# Cpcis_connectors_P1_P6.net
KiCad netlist of a schematic drawn in Altium Designer
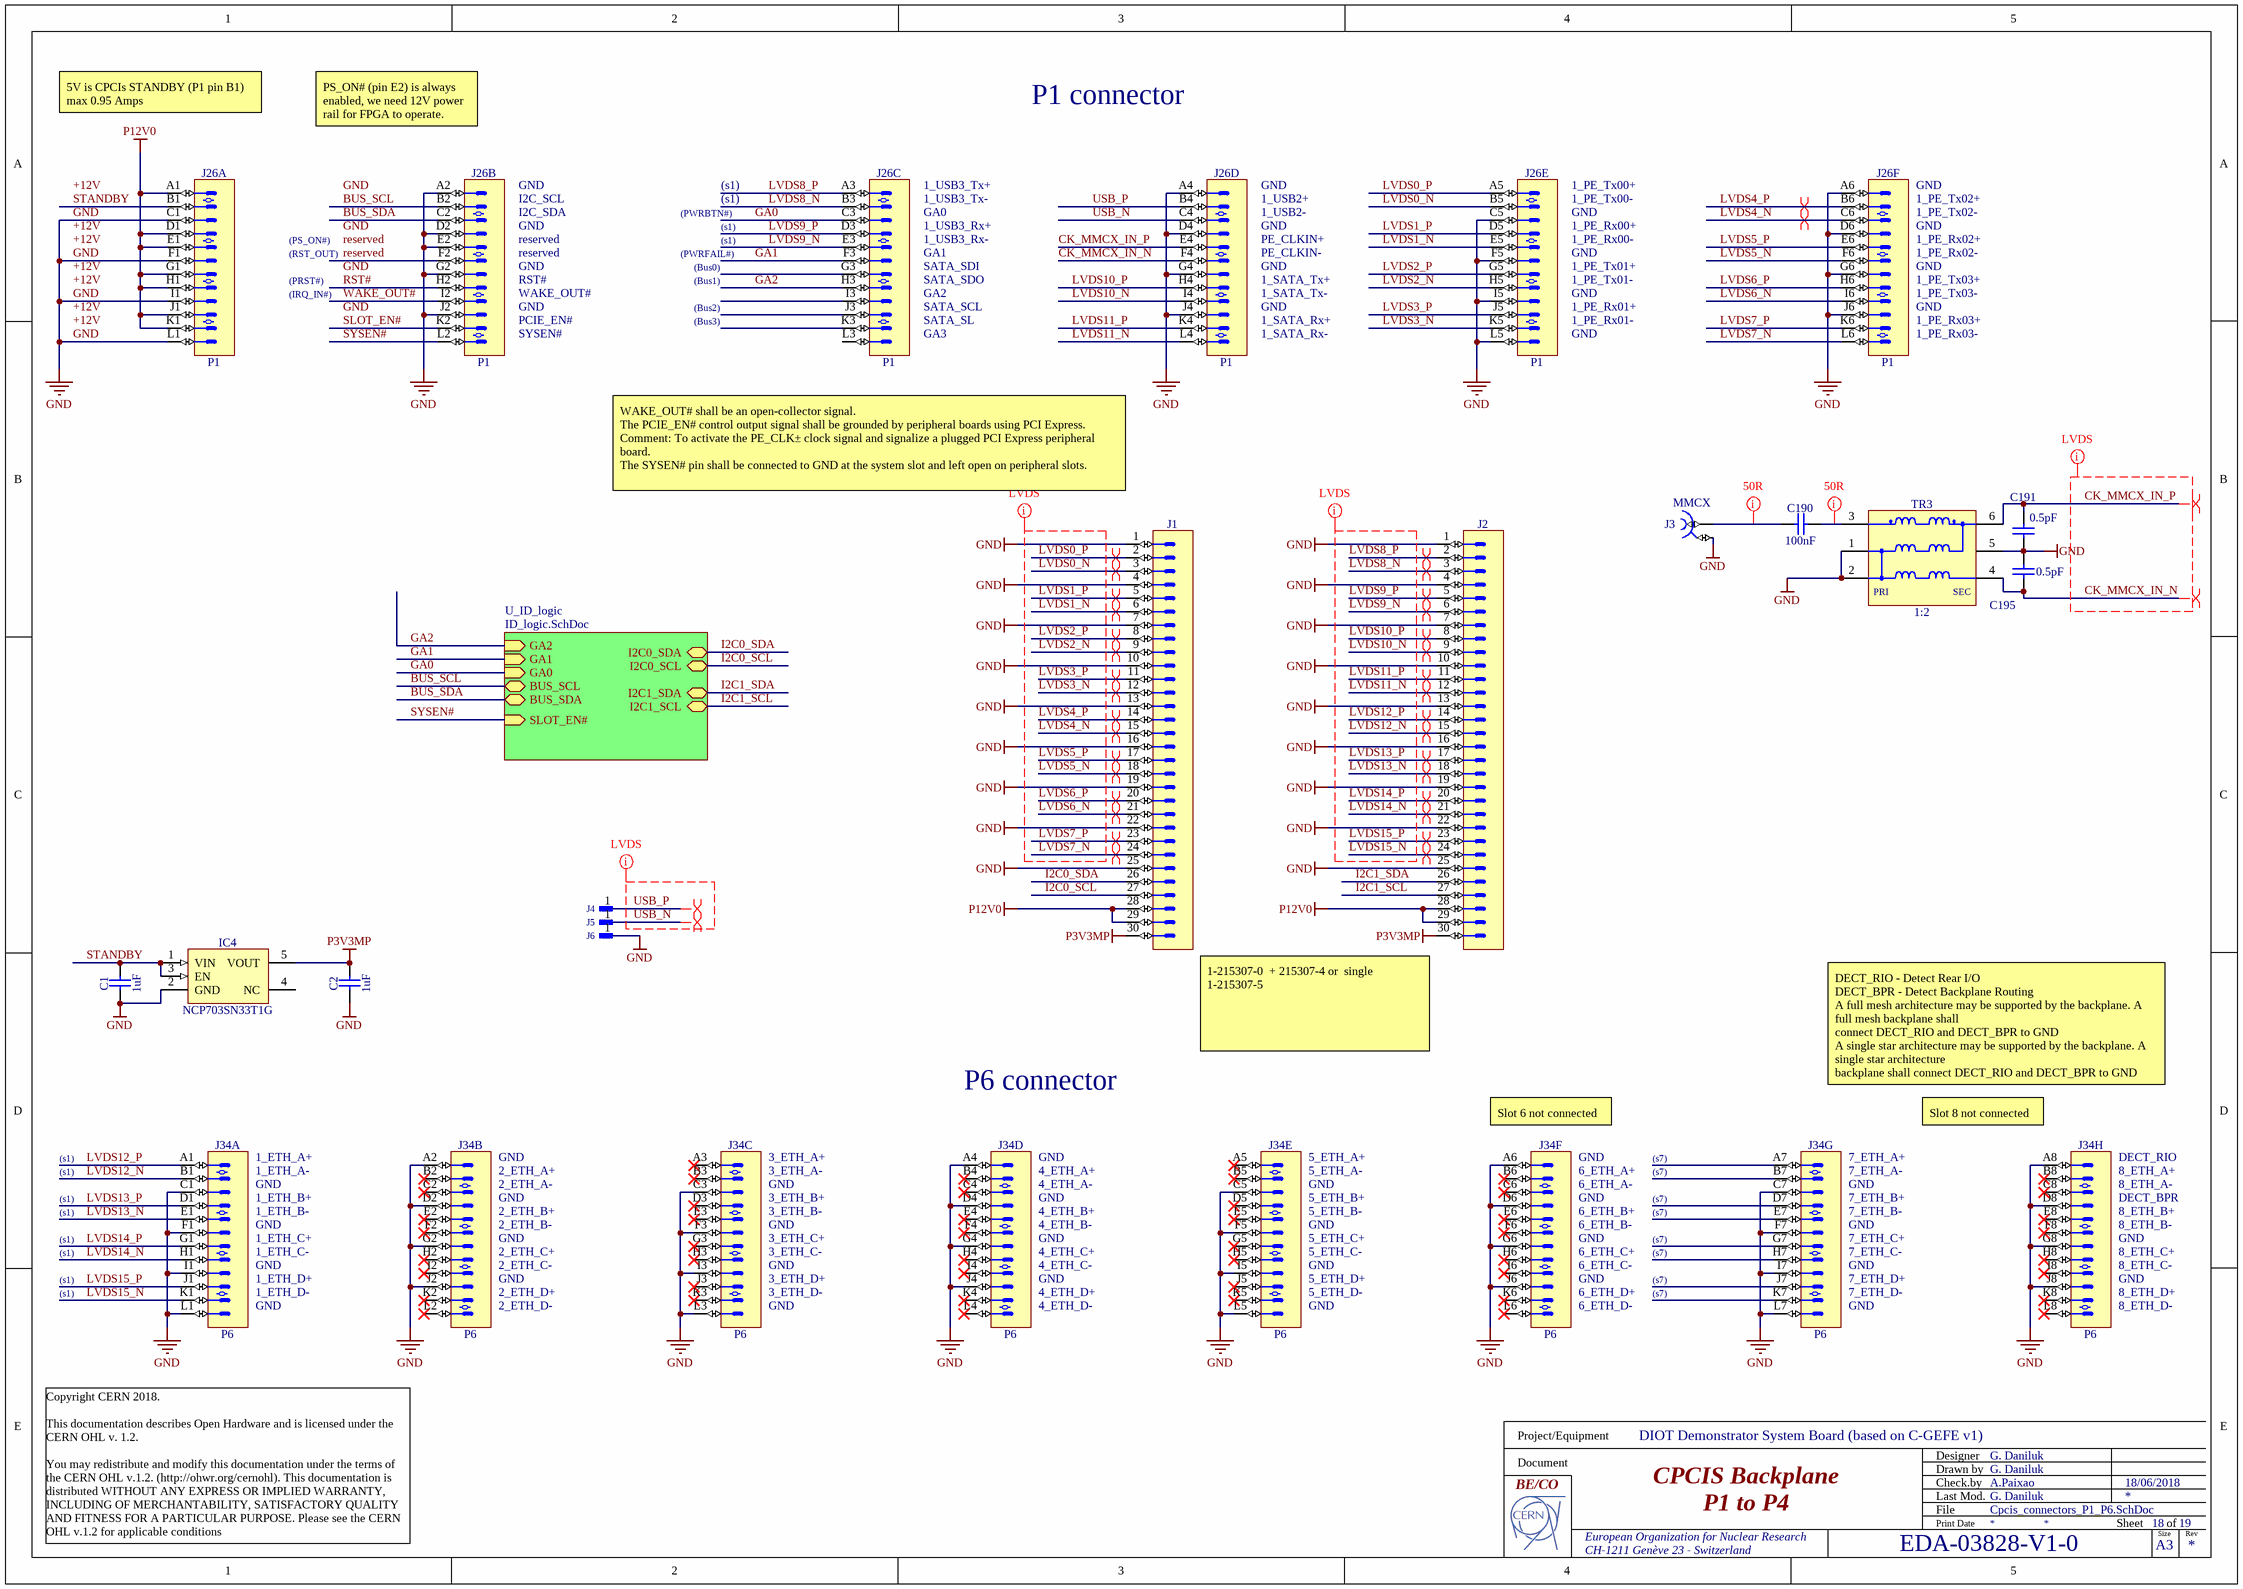
[diagram p0: Cpcis_connectors_P1_P6.SchDoc]

(export (version "E")
  (design (tool "Eeschema 10.0.6"))
  (components
    (comp (ref "C1")
      (value "1uF")
      (footprint "CAPC2012X140N")
      (description "Non-polarised capacitor")
      (fields
        (field (name "PART NUMBER") "CC0805_1UF_35V_20%_X7R")
        (field (name "VOLTAGE") "35V")
        (field (name "AUTHOR") "CERN DEM JLC")
      )
      (libsource (lib "Capacitors") (part "Capacitor - non polarized"))
    )
    (comp (ref "C2")
      (value "1uF")
      (footprint "CAPC2012X140N")
      (description "Non-polarised capacitor")
      (fields
        (field (name "PART NUMBER") "CC0805_1UF_35V_20%_X7R")
        (field (name "VOLTAGE") "35V")
        (field (name "AUTHOR") "CERN DEM JLC")
      )
      (libsource (lib "Capacitors") (part "Capacitor - non polarized"))
    )
    (comp (ref "C190")
      (value "100nF")
      (footprint "CAPC1005X55N")
      (description "Non-polarised capacitor")
      (fields
        (field (name "PART NUMBER") "CC0402_100NF_16V_10%_X5R")
        (field (name "VOLTAGE") "16V")
        (field (name "AUTHOR") "CERN DEM JLC")
      )
      (libsource (lib "Capacitors") (part "Capacitor - non polarized"))
    )
    (comp (ref "C191")
      (value "0.5pF")
      (footprint "CAPC1005X50N")
      (description "Non-polarised capacitor")
      (fields
        (field (name "PART NUMBER") "CC0402_0.5PF_25V_0.05PF_AVX_04023J0R5ABSTR")
        (field (name "VOLTAGE") "25V")
        (field (name "AUTHOR") "CERN DEM JLC")
      )
      (libsource (lib "Capacitors") (part "Capacitor - non polarized"))
    )
    (comp (ref "C195")
      (value "0.5pF")
      (footprint "CAPC1005X50N")
      (description "Non-polarised capacitor")
      (fields
        (field (name "PART NUMBER") "CC0402_0.5PF_25V_0.05PF_AVX_04023J0R5ABSTR")
        (field (name "VOLTAGE") "25V")
        (field (name "AUTHOR") "CERN DEM JLC")
      )
      (libsource (lib "Capacitors") (part "Capacitor - non polarized"))
    )
    (comp (ref "IC4")
      (value "NCP703SN33T1G")
      (footprint "SOT95P275X110-5N")
      (description "3.3V 300mA, Ultra-Low Quiescent Current, IQ 12uA, Ultra-Low Noise, LDO Voltage Regulator")
      (fields (field (name "MANUFACTURER") "ON SEMICONDUCTOR") (field (name "AUTHOR") "CERN DEM JLC"))
      (libsource (lib "ICs And Semiconductors") (part "NCP703SN"))
    )
    (comp (ref "J1")
      (value "AMPMODU")
      (footprint "TYCO_1-215307-5")
      (description "Connector 2.54mm, 30 pin female, vertical, 7mm, AMPMODU HV-100/HV-190")
      (fields
        (field (name "PART NUMBER") "TYCO_1-215307-5")
        (field (name "MANUFACTURER") "TYCO ELECTRONICS")
        (field (name "AUTHOR") "GK")
      )
      (libsource (lib "LIBRARY_SCH") (part "CON_2x15_2.54_female_V_mirror"))
    )
    (comp (ref "J2")
      (value "AMPMODU")
      (footprint "TYCO_1-215307-5")
      (description "Connector 2.54mm, 30 pin female, vertical, 7mm, AMPMODU HV-100/HV-190")
      (fields
        (field (name "PART NUMBER") "TYCO_1-215307-5")
        (field (name "MANUFACTURER") "TYCO ELECTRONICS")
        (field (name "AUTHOR") "GK")
      )
      (libsource (lib "LIBRARY_SCH") (part "CON_2x15_2.54_female_V_mirror"))
    )
    (comp (ref "J3")
      (value "Coax_1Female_1Shield")
      (footprint "HUBER-SUHNER_85_MMCX-50-0-1/111_OE")
      (fields
        (field (name "PART NUMBER") "HUBER-SUHNER_85_MMCX-50-0-1/111_OE")
        (field (name "FAMILY") "MMCX")
        (field (name "MANUFACTURER") "HUBER+SUHNER")
        (field (name "MANUFACTURER PART NUMBER") "85_MMCX-50-0-1/111_OE")
        (field (name "AUTHOR") "CERN DEM JLC")
      )
      (libsource (lib "Connectors") (part "Coax_1Female_1Shield"))
    )
    (comp (ref "J4")
      (value "SMD Pad")
      (footprint "R700X200")
      (description "Single SMD Pad Standard")
      (fields (field (name "PART NUMBER") "TEST1_CompoKind") (field (name "AUTHOR") "CERN DEM MR"))
      (libsource (lib "Eletro-mechanical") (part "Single SMD Pad Standard"))
    )
    (comp (ref "J5")
      (value "SMD Pad")
      (footprint "R700X200")
      (description "Single SMD Pad Standard")
      (fields (field (name "PART NUMBER") "TEST1_CompoKind") (field (name "AUTHOR") "CERN DEM MR"))
      (libsource (lib "Eletro-mechanical") (part "Single SMD Pad Standard"))
    )
    (comp (ref "J6")
      (value "SMD Pad")
      (footprint "R700X200")
      (description "Single SMD Pad Standard")
      (fields (field (name "PART NUMBER") "TEST1_CompoKind") (field (name "AUTHOR") "CERN DEM MR"))
      (libsource (lib "Eletro-mechanical") (part "Single SMD Pad Standard"))
    )
    (comp (ref "J26")
      (value "P1")
      (footprint "AMPHENOL_10052825-101LF")
      (description "72 Contacts Header, 6 Columns, 4 Pairs per Column")
      (fields
        (field (name "PART NUMBER") "AMPHENOL_10052825-101LF")
        (field (name "MANUFACTURER") "AMPHENOL")
        (field (name "AUTHOR") "CERN DEM MR")
      )
      (libsource (lib "Connectors") (part "AMPHENOL_10052825-101LF"))
    )
    (comp (ref "J34")
      (value "P6")
      (footprint "AMPHENOL_10052838-101LF")
      (description "96 Contacts Header, 8 Columns, 4 Pairs per Column")
      (fields
        (field (name "PART NUMBER") "AMPHENOL_10052838-101LF")
        (field (name "MANUFACTURER") "AMPHENOL")
        (field (name "AUTHOR") "CERN DEM MR")
      )
      (libsource (lib "Connectors") (part "AMPHENOL_10052838-101LF"))
    )
    (comp (ref "TR3")
      (value "1:2")
      (footprint "XFMR_MINI-CIRCUITS_DB1627")
      (description "50 OHMS 10 to 4000 MHz RF Transformer")
      (fields
        (field (name "PART NUMBER") "XFMR_MINI-CIRCUITS_TCM2-43X+")
        (field (name "POWER") "0.4W")
        (field (name "AUTHOR") "CERN DEM BC")
      )
      (libsource (lib "Inductors & Transformers") (part "XFMR_MINI-CIRCUITS_TCM2-43X"))
    )
  )
  (nets
    (net (code "2") (name "/BUS_SCL") (class "Default")
      (node (ref "J26") (pin "B2") (pinfunction "B2_B2") (pintype "bidirectional"))
    )
    (net (code "3") (name "/BUS_SDA") (class "Default")
      (node (ref "J26") (pin "C2") (pinfunction "C2_C2") (pintype "bidirectional"))
    )
    (net (code "4") (name "/CK_MMCX_IN_N") (class "Default")
      (node (ref "C195") (pin "1") (pinfunction "1_1") (pintype "passive"))
      (node (ref "J26") (pin "F4") (pinfunction "F4_F4") (pintype "bidirectional"))
      (node (ref "TR3") (pin "4") (pinfunction "S1_4") (pintype "passive"))
    )
    (net (code "5") (name "/CK_MMCX_IN_P") (class "Default")
      (node (ref "C191") (pin "2") (pinfunction "2_2") (pintype "passive"))
      (node (ref "J26") (pin "E4") (pinfunction "E4_E4") (pintype "bidirectional"))
      (node (ref "TR3") (pin "6") (pinfunction "S1_6") (pintype "passive"))
    )
    (net (code "6") (name "/GA0") (class "Default")
      (node (ref "J26") (pin "C3") (pinfunction "C3_C3") (pintype "bidirectional"))
    )
    (net (code "7") (name "/GA1") (class "Default")
      (node (ref "J26") (pin "F3") (pinfunction "F3_F3") (pintype "bidirectional"))
    )
    (net (code "8") (name "/GA2") (class "Default")
      (node (ref "J26") (pin "H3") (pinfunction "H3_H3") (pintype "bidirectional"))
    )
    (net (code "9") (name "/I2C0_SCL") (class "Default")
      (node (ref "J1") (pin "27") (pinfunction "27_27") (pintype "bidirectional"))
    )
    (net (code "10") (name "/I2C0_SDA") (class "Default")
      (node (ref "J1") (pin "26") (pinfunction "26_26") (pintype "bidirectional"))
    )
    (net (code "11") (name "/I2C1_SCL") (class "Default")
      (node (ref "J2") (pin "27") (pinfunction "27_27") (pintype "bidirectional"))
    )
    (net (code "12") (name "/I2C1_SDA") (class "Default")
      (node (ref "J2") (pin "26") (pinfunction "26_26") (pintype "bidirectional"))
    )
    (net (code "13") (name "/LVDS0_N") (class "Default")
      (node (ref "J1") (pin "3") (pinfunction "3_3") (pintype "bidirectional"))
      (node (ref "J26") (pin "B5") (pinfunction "B5_B5") (pintype "bidirectional"))
    )
    (net (code "14") (name "/LVDS0_P") (class "Default")
      (node (ref "J1") (pin "2") (pinfunction "2_2") (pintype "bidirectional"))
      (node (ref "J26") (pin "A5") (pinfunction "A5_A5") (pintype "bidirectional"))
    )
    (net (code "15") (name "/LVDS1_N") (class "Default")
      (node (ref "J1") (pin "6") (pinfunction "6_6") (pintype "bidirectional"))
      (node (ref "J26") (pin "E5") (pinfunction "E5_E5") (pintype "bidirectional"))
    )
    (net (code "16") (name "/LVDS1_P") (class "Default")
      (node (ref "J1") (pin "5") (pinfunction "5_5") (pintype "bidirectional"))
      (node (ref "J26") (pin "D5") (pinfunction "D5_D5") (pintype "bidirectional"))
    )
    (net (code "17") (name "/LVDS2_N") (class "Default")
      (node (ref "J1") (pin "9") (pinfunction "9_9") (pintype "bidirectional"))
      (node (ref "J26") (pin "H5") (pinfunction "H5_H5") (pintype "bidirectional"))
    )
    (net (code "18") (name "/LVDS2_P") (class "Default")
      (node (ref "J1") (pin "8") (pinfunction "8_8") (pintype "bidirectional"))
      (node (ref "J26") (pin "G5") (pinfunction "G5_G5") (pintype "bidirectional"))
    )
    (net (code "19") (name "/LVDS3_N") (class "Default")
      (node (ref "J1") (pin "12") (pinfunction "12_12") (pintype "bidirectional"))
      (node (ref "J26") (pin "K5") (pinfunction "K5_K5") (pintype "bidirectional"))
    )
    (net (code "20") (name "/LVDS3_P") (class "Default")
      (node (ref "J1") (pin "11") (pinfunction "11_11") (pintype "bidirectional"))
      (node (ref "J26") (pin "J5") (pinfunction "J5_J5") (pintype "bidirectional"))
    )
    (net (code "21") (name "/LVDS4_N") (class "Default")
      (node (ref "J1") (pin "15") (pinfunction "15_15") (pintype "bidirectional"))
      (node (ref "J26") (pin "C6") (pinfunction "C6_C6") (pintype "bidirectional"))
    )
    (net (code "22") (name "/LVDS4_P") (class "Default")
      (node (ref "J1") (pin "14") (pinfunction "14_14") (pintype "bidirectional"))
      (node (ref "J26") (pin "B6") (pinfunction "B6_B6") (pintype "bidirectional"))
    )
    (net (code "23") (name "/LVDS5_N") (class "Default")
      (node (ref "J1") (pin "18") (pinfunction "18_18") (pintype "bidirectional"))
      (node (ref "J26") (pin "F6") (pinfunction "F6_F6") (pintype "bidirectional"))
    )
    (net (code "24") (name "/LVDS5_P") (class "Default")
      (node (ref "J1") (pin "17") (pinfunction "17_17") (pintype "bidirectional"))
      (node (ref "J26") (pin "E6") (pinfunction "E6_E6") (pintype "bidirectional"))
    )
    (net (code "25") (name "/LVDS6_N") (class "Default")
      (node (ref "J1") (pin "21") (pinfunction "21_21") (pintype "bidirectional"))
      (node (ref "J26") (pin "I6") (pinfunction "I6_I6") (pintype "bidirectional"))
    )
    (net (code "26") (name "/LVDS6_P") (class "Default")
      (node (ref "J1") (pin "20") (pinfunction "20_20") (pintype "bidirectional"))
      (node (ref "J26") (pin "H6") (pinfunction "H6_H6") (pintype "bidirectional"))
    )
    (net (code "27") (name "/LVDS7_N") (class "Default")
      (node (ref "J1") (pin "24") (pinfunction "24_24") (pintype "bidirectional"))
      (node (ref "J26") (pin "L6") (pinfunction "L6_L6") (pintype "bidirectional"))
    )
    (net (code "28") (name "/LVDS7_P") (class "Default")
      (node (ref "J1") (pin "23") (pinfunction "23_23") (pintype "bidirectional"))
      (node (ref "J26") (pin "K6") (pinfunction "K6_K6") (pintype "bidirectional"))
    )
    (net (code "29") (name "/LVDS8_N") (class "Default")
      (node (ref "J2") (pin "3") (pinfunction "3_3") (pintype "bidirectional"))
      (node (ref "J26") (pin "B3") (pinfunction "B3_B3") (pintype "bidirectional"))
    )
    (net (code "30") (name "/LVDS8_P") (class "Default")
      (node (ref "J2") (pin "2") (pinfunction "2_2") (pintype "bidirectional"))
      (node (ref "J26") (pin "A3") (pinfunction "A3_A3") (pintype "bidirectional"))
    )
    (net (code "31") (name "/LVDS9_N") (class "Default")
      (node (ref "J2") (pin "6") (pinfunction "6_6") (pintype "bidirectional"))
      (node (ref "J26") (pin "E3") (pinfunction "E3_E3") (pintype "bidirectional"))
    )
    (net (code "32") (name "/LVDS9_P") (class "Default")
      (node (ref "J2") (pin "5") (pinfunction "5_5") (pintype "bidirectional"))
      (node (ref "J26") (pin "D3") (pinfunction "D3_D3") (pintype "bidirectional"))
    )
    (net (code "33") (name "/LVDS10_N") (class "Default")
      (node (ref "J2") (pin "9") (pinfunction "9_9") (pintype "bidirectional"))
      (node (ref "J26") (pin "I4") (pinfunction "I4_I4") (pintype "bidirectional"))
    )
    (net (code "34") (name "/LVDS10_P") (class "Default")
      (node (ref "J2") (pin "8") (pinfunction "8_8") (pintype "bidirectional"))
      (node (ref "J26") (pin "H4") (pinfunction "H4_H4") (pintype "bidirectional"))
    )
    (net (code "35") (name "/LVDS11_N") (class "Default")
      (node (ref "J2") (pin "12") (pinfunction "12_12") (pintype "bidirectional"))
      (node (ref "J26") (pin "L4") (pinfunction "L4_L4") (pintype "bidirectional"))
    )
    (net (code "36") (name "/LVDS11_P") (class "Default")
      (node (ref "J2") (pin "11") (pinfunction "11_11") (pintype "bidirectional"))
      (node (ref "J26") (pin "K4") (pinfunction "K4_K4") (pintype "bidirectional"))
    )
    (net (code "37") (name "/LVDS12_N") (class "Default")
      (node (ref "J2") (pin "15") (pinfunction "15_15") (pintype "bidirectional"))
      (node (ref "J34") (pin "B1") (pinfunction "B1_B1") (pintype "bidirectional"))
    )
    (net (code "38") (name "/LVDS12_P") (class "Default")
      (node (ref "J2") (pin "14") (pinfunction "14_14") (pintype "bidirectional"))
      (node (ref "J34") (pin "A1") (pinfunction "A1_A1") (pintype "bidirectional"))
    )
    (net (code "39") (name "/LVDS13_N") (class "Default")
      (node (ref "J2") (pin "18") (pinfunction "18_18") (pintype "bidirectional"))
      (node (ref "J34") (pin "E1") (pinfunction "E1_E1") (pintype "bidirectional"))
    )
    (net (code "40") (name "/LVDS13_P") (class "Default")
      (node (ref "J2") (pin "17") (pinfunction "17_17") (pintype "bidirectional"))
      (node (ref "J34") (pin "D1") (pinfunction "D1_D1") (pintype "bidirectional"))
    )
    (net (code "41") (name "/LVDS14_N") (class "Default")
      (node (ref "J2") (pin "21") (pinfunction "21_21") (pintype "bidirectional"))
      (node (ref "J34") (pin "H1") (pinfunction "H1_H1") (pintype "bidirectional"))
    )
    (net (code "42") (name "/LVDS14_P") (class "Default")
      (node (ref "J2") (pin "20") (pinfunction "20_20") (pintype "bidirectional"))
      (node (ref "J34") (pin "G1") (pinfunction "G1_G1") (pintype "bidirectional"))
    )
    (net (code "43") (name "/LVDS15_N") (class "Default")
      (node (ref "J2") (pin "24") (pinfunction "24_24") (pintype "bidirectional"))
      (node (ref "J34") (pin "K1") (pinfunction "K1_K1") (pintype "bidirectional"))
    )
    (net (code "44") (name "/LVDS15_P") (class "Default")
      (node (ref "J2") (pin "23") (pinfunction "23_23") (pintype "bidirectional"))
      (node (ref "J34") (pin "J1") (pinfunction "J1_J1") (pintype "bidirectional"))
    )
    (net (code "45") (name "/RST#") (class "Default")
      (node (ref "J26") (pin "H2") (pinfunction "H2_H2") (pintype "bidirectional"))
    )
    (net (code "46") (name "/SLOT_EN#") (class "Default")
      (node (ref "J26") (pin "K2") (pinfunction "K2_K2") (pintype "bidirectional"))
    )
    (net (code "47") (name "/STANDBY") (class "Default")
      (node (ref "C1") (pin "2") (pinfunction "2_2") (pintype "passive"))
      (node (ref "IC4") (pin "1") (pinfunction "VIN_1") (pintype "input"))
      (node (ref "IC4") (pin "3") (pinfunction "EN_3") (pintype "input"))
      (node (ref "J26") (pin "B1") (pinfunction "B1_B1") (pintype "bidirectional"))
    )
    (net (code "48") (name "/SYSEN#") (class "Default")
      (node (ref "J26") (pin "L2") (pinfunction "L2_L2") (pintype "bidirectional"))
    )
    (net (code "49") (name "/USB_N") (class "Default")
      (node (ref "J26") (pin "C4") (pinfunction "C4_C4") (pintype "bidirectional"))
      (node (ref "J5") (pin "1") (pinfunction "1_1") (pintype "bidirectional"))
    )
    (net (code "50") (name "/USB_P") (class "Default")
      (node (ref "J26") (pin "B4") (pinfunction "B4_B4") (pintype "bidirectional"))
      (node (ref "J4") (pin "1") (pinfunction "1_1") (pintype "bidirectional"))
    )
    (net (code "51") (name "/WAKE_OUT#") (class "Default")
      (node (ref "J26") (pin "I2") (pinfunction "I2_I2") (pintype "bidirectional"))
    )
    (net (code "52") (name "/reserved") (class "Default")
      (node (ref "J26") (pin "F2") (pinfunction "F2_F2") (pintype "bidirectional"))
    )
    (net (code "53") (name "GND") (class "Default")
      (node (ref "C1") (pin "1") (pinfunction "1_1") (pintype "passive"))
      (node (ref "C191") (pin "1") (pinfunction "1_1") (pintype "passive"))
      (node (ref "C195") (pin "2") (pinfunction "2_2") (pintype "passive"))
      (node (ref "C2") (pin "1") (pinfunction "1_1") (pintype "passive"))
      (node (ref "IC4") (pin "2") (pinfunction "GND_2") (pintype "power_in"))
      (node (ref "J1") (pin "1") (pinfunction "1_1") (pintype "bidirectional"))
      (node (ref "J1") (pin "10") (pinfunction "10_10") (pintype "bidirectional"))
      (node (ref "J1") (pin "13") (pinfunction "13_13") (pintype "bidirectional"))
      (node (ref "J1") (pin "16") (pinfunction "16_16") (pintype "bidirectional"))
      (node (ref "J1") (pin "19") (pinfunction "19_19") (pintype "bidirectional"))
      (node (ref "J1") (pin "22") (pinfunction "22_22") (pintype "bidirectional"))
      (node (ref "J1") (pin "25") (pinfunction "25_25") (pintype "bidirectional"))
      (node (ref "J1") (pin "4") (pinfunction "4_4") (pintype "bidirectional"))
      (node (ref "J1") (pin "7") (pinfunction "7_7") (pintype "bidirectional"))
      (node (ref "J2") (pin "1") (pinfunction "1_1") (pintype "bidirectional"))
      (node (ref "J2") (pin "10") (pinfunction "10_10") (pintype "bidirectional"))
      (node (ref "J2") (pin "13") (pinfunction "13_13") (pintype "bidirectional"))
      (node (ref "J2") (pin "16") (pinfunction "16_16") (pintype "bidirectional"))
      (node (ref "J2") (pin "19") (pinfunction "19_19") (pintype "bidirectional"))
      (node (ref "J2") (pin "22") (pinfunction "22_22") (pintype "bidirectional"))
      (node (ref "J2") (pin "25") (pinfunction "25_25") (pintype "bidirectional"))
      (node (ref "J2") (pin "4") (pinfunction "4_4") (pintype "bidirectional"))
      (node (ref "J2") (pin "7") (pinfunction "7_7") (pintype "bidirectional"))
      (node (ref "J26") (pin "A2") (pinfunction "A2_A2") (pintype "bidirectional"))
      (node (ref "J26") (pin "A4") (pinfunction "A4_A4") (pintype "bidirectional"))
      (node (ref "J26") (pin "A6") (pinfunction "A6_A6") (pintype "bidirectional"))
      (node (ref "J26") (pin "C1") (pinfunction "C1_C1") (pintype "bidirectional"))
      (node (ref "J26") (pin "C5") (pinfunction "C5_C5") (pintype "bidirectional"))
      (node (ref "J26") (pin "D2") (pinfunction "D2_D2") (pintype "bidirectional"))
      (node (ref "J26") (pin "D4") (pinfunction "D4_D4") (pintype "bidirectional"))
      (node (ref "J26") (pin "D6") (pinfunction "D6_D6") (pintype "bidirectional"))
      (node (ref "J26") (pin "E2") (pinfunction "E2_E2") (pintype "bidirectional"))
      (node (ref "J26") (pin "F1") (pinfunction "F1_F1") (pintype "bidirectional"))
      (node (ref "J26") (pin "F5") (pinfunction "F5_F5") (pintype "bidirectional"))
      (node (ref "J26") (pin "G2") (pinfunction "G2_G2") (pintype "bidirectional"))
      (node (ref "J26") (pin "G4") (pinfunction "G4_G4") (pintype "bidirectional"))
      (node (ref "J26") (pin "G6") (pinfunction "G6_G6") (pintype "bidirectional"))
      (node (ref "J26") (pin "I1") (pinfunction "I1_I1") (pintype "bidirectional"))
      (node (ref "J26") (pin "I5") (pinfunction "I5_I5") (pintype "bidirectional"))
      (node (ref "J26") (pin "J2") (pinfunction "J2_J2") (pintype "bidirectional"))
      (node (ref "J26") (pin "J4") (pinfunction "J4_J4") (pintype "bidirectional"))
      (node (ref "J26") (pin "J6") (pinfunction "J6_J6") (pintype "bidirectional"))
      (node (ref "J26") (pin "L1") (pinfunction "L1_L1") (pintype "bidirectional"))
      (node (ref "J26") (pin "L5") (pinfunction "L5_L5") (pintype "bidirectional"))
      (node (ref "J3") (pin "2") (pinfunction "2_2") (pintype "bidirectional"))
      (node (ref "J34") (pin "A2") (pinfunction "A2_A2") (pintype "bidirectional"))
      (node (ref "J34") (pin "A4") (pinfunction "A4_A4") (pintype "bidirectional"))
      (node (ref "J34") (pin "A6") (pinfunction "A6_A6") (pintype "bidirectional"))
      (node (ref "J34") (pin "A8") (pinfunction "A8_A8") (pintype "bidirectional"))
      (node (ref "J34") (pin "C1") (pinfunction "C1_C1") (pintype "bidirectional"))
      (node (ref "J34") (pin "C3") (pinfunction "C3_C3") (pintype "bidirectional"))
      (node (ref "J34") (pin "C5") (pinfunction "C5_C5") (pintype "bidirectional"))
      (node (ref "J34") (pin "C7") (pinfunction "C7_C7") (pintype "bidirectional"))
      (node (ref "J34") (pin "D2") (pinfunction "D2_D2") (pintype "bidirectional"))
      (node (ref "J34") (pin "D4") (pinfunction "D4_D4") (pintype "bidirectional"))
      (node (ref "J34") (pin "D6") (pinfunction "D6_D6") (pintype "bidirectional"))
      (node (ref "J34") (pin "D8") (pinfunction "D8_D8") (pintype "bidirectional"))
      (node (ref "J34") (pin "F1") (pinfunction "F1_F1") (pintype "bidirectional"))
      (node (ref "J34") (pin "F3") (pinfunction "F3_F3") (pintype "bidirectional"))
      (node (ref "J34") (pin "F5") (pinfunction "F5_F5") (pintype "bidirectional"))
      (node (ref "J34") (pin "F7") (pinfunction "F7_F7") (pintype "bidirectional"))
      (node (ref "J34") (pin "G2") (pinfunction "G2_G2") (pintype "bidirectional"))
      (node (ref "J34") (pin "G4") (pinfunction "G4_G4") (pintype "bidirectional"))
      (node (ref "J34") (pin "G6") (pinfunction "G6_G6") (pintype "bidirectional"))
      (node (ref "J34") (pin "G8") (pinfunction "G8_G8") (pintype "bidirectional"))
      (node (ref "J34") (pin "I1") (pinfunction "I1_I1") (pintype "bidirectional"))
      (node (ref "J34") (pin "I3") (pinfunction "I3_I3") (pintype "bidirectional"))
      (node (ref "J34") (pin "I5") (pinfunction "I5_I5") (pintype "bidirectional"))
      (node (ref "J34") (pin "I7") (pinfunction "I7_I7") (pintype "bidirectional"))
      (node (ref "J34") (pin "J2") (pinfunction "J2_J2") (pintype "bidirectional"))
      (node (ref "J34") (pin "J4") (pinfunction "J4_J4") (pintype "bidirectional"))
      (node (ref "J34") (pin "J6") (pinfunction "J6_J6") (pintype "bidirectional"))
      (node (ref "J34") (pin "J8") (pinfunction "J8_J8") (pintype "bidirectional"))
      (node (ref "J34") (pin "L1") (pinfunction "L1_L1") (pintype "bidirectional"))
      (node (ref "J34") (pin "L3") (pinfunction "L3_L3") (pintype "bidirectional"))
      (node (ref "J34") (pin "L5") (pinfunction "L5_L5") (pintype "bidirectional"))
      (node (ref "J34") (pin "L7") (pinfunction "L7_L7") (pintype "bidirectional"))
      (node (ref "J6") (pin "1") (pinfunction "1_1") (pintype "bidirectional"))
      (node (ref "TR3") (pin "1") (pinfunction "P1_1") (pintype "passive"))
      (node (ref "TR3") (pin "2") (pinfunction "P1_2") (pintype "passive"))
      (node (ref "TR3") (pin "5") (pinfunction "NC_5") (pintype "passive"))
    )
    (net (code "54") (name "Net-(C190-Pad1)") (class "Default")
      (node (ref "C190") (pin "1") (pinfunction "1_1") (pintype "passive"))
      (node (ref "J3") (pin "1") (pinfunction "1_1") (pintype "bidirectional"))
    )
    (net (code "55") (name "Net-(C190-Pad2)") (class "Default")
      (node (ref "C190") (pin "2") (pinfunction "2_2") (pintype "passive"))
      (node (ref "TR3") (pin "3") (pinfunction "P1_3") (pintype "passive"))
    )
    (net (code "56") (name "P3V3MP") (class "Default")
      (node (ref "C2") (pin "2") (pinfunction "2_2") (pintype "passive"))
      (node (ref "IC4") (pin "5") (pinfunction "VOUT_5") (pintype "power_in"))
      (node (ref "J1") (pin "30") (pinfunction "30_30") (pintype "bidirectional"))
      (node (ref "J2") (pin "30") (pinfunction "30_30") (pintype "bidirectional"))
    )
    (net (code "57") (name "P12V0") (class "Default")
      (node (ref "J1") (pin "28") (pinfunction "28_28") (pintype "bidirectional"))
      (node (ref "J1") (pin "29") (pinfunction "29_29") (pintype "bidirectional"))
      (node (ref "J2") (pin "28") (pinfunction "28_28") (pintype "bidirectional"))
      (node (ref "J2") (pin "29") (pinfunction "29_29") (pintype "bidirectional"))
      (node (ref "J26") (pin "A1") (pinfunction "A1_A1") (pintype "bidirectional"))
      (node (ref "J26") (pin "D1") (pinfunction "D1_D1") (pintype "bidirectional"))
      (node (ref "J26") (pin "E1") (pinfunction "E1_E1") (pintype "bidirectional"))
      (node (ref "J26") (pin "G1") (pinfunction "G1_G1") (pintype "bidirectional"))
      (node (ref "J26") (pin "H1") (pinfunction "H1_H1") (pintype "bidirectional"))
      (node (ref "J26") (pin "J1") (pinfunction "J1_J1") (pintype "bidirectional"))
      (node (ref "J26") (pin "K1") (pinfunction "K1_K1") (pintype "bidirectional"))
    )
    (net (code "58") (name "unconnected-(IC4-NC-Pad4)") (class "Default")
      (node (ref "IC4") (pin "4") (pinfunction "NC_4") (pintype "passive"))
    )
    (net (code "59") (name "unconnected-(J26-PadG3)") (class "Default")
      (node (ref "J26") (pin "G3") (pinfunction "G3_G3") (pintype "bidirectional"))
    )
    (net (code "60") (name "unconnected-(J26-PadI3)") (class "Default")
      (node (ref "J26") (pin "I3") (pinfunction "I3_I3") (pintype "bidirectional"))
    )
    (net (code "61") (name "unconnected-(J26-PadJ3)") (class "Default")
      (node (ref "J26") (pin "J3") (pinfunction "J3_J3") (pintype "bidirectional"))
    )
    (net (code "62") (name "unconnected-(J26-PadK3)") (class "Default")
      (node (ref "J26") (pin "K3") (pinfunction "K3_K3") (pintype "bidirectional"))
    )
    (net (code "63") (name "unconnected-(J26-PadL3)") (class "Default")
      (node (ref "J26") (pin "L3") (pinfunction "L3_L3") (pintype "bidirectional"))
    )
    (net (code "64") (name "unconnected-(J34-PadA3)") (class "Default")
      (node (ref "J34") (pin "A3") (pinfunction "A3_A3") (pintype "bidirectional+no_connect"))
    )
    (net (code "65") (name "unconnected-(J34-PadA5)") (class "Default")
      (node (ref "J34") (pin "A5") (pinfunction "A5_A5") (pintype "bidirectional+no_connect"))
    )
    (net (code "66") (name "unconnected-(J34-PadA7)") (class "Default")
      (node (ref "J34") (pin "A7") (pinfunction "A7_A7") (pintype "bidirectional"))
    )
    (net (code "67") (name "unconnected-(J34-PadB2)") (class "Default")
      (node (ref "J34") (pin "B2") (pinfunction "B2_B2") (pintype "bidirectional+no_connect"))
    )
    (net (code "68") (name "unconnected-(J34-PadB3)") (class "Default")
      (node (ref "J34") (pin "B3") (pinfunction "B3_B3") (pintype "bidirectional+no_connect"))
    )
    (net (code "69") (name "unconnected-(J34-PadB4)") (class "Default")
      (node (ref "J34") (pin "B4") (pinfunction "B4_B4") (pintype "bidirectional+no_connect"))
    )
    (net (code "70") (name "unconnected-(J34-PadB5)") (class "Default")
      (node (ref "J34") (pin "B5") (pinfunction "B5_B5") (pintype "bidirectional+no_connect"))
    )
    (net (code "71") (name "unconnected-(J34-PadB6)") (class "Default")
      (node (ref "J34") (pin "B6") (pinfunction "B6_B6") (pintype "bidirectional+no_connect"))
    )
    (net (code "72") (name "unconnected-(J34-PadB7)") (class "Default")
      (node (ref "J34") (pin "B7") (pinfunction "B7_B7") (pintype "bidirectional"))
    )
    (net (code "73") (name "unconnected-(J34-PadB8)") (class "Default")
      (node (ref "J34") (pin "B8") (pinfunction "B8_B8") (pintype "bidirectional+no_connect"))
    )
    (net (code "74") (name "unconnected-(J34-PadC2)") (class "Default")
      (node (ref "J34") (pin "C2") (pinfunction "C2_C2") (pintype "bidirectional+no_connect"))
    )
    (net (code "75") (name "unconnected-(J34-PadC4)") (class "Default")
      (node (ref "J34") (pin "C4") (pinfunction "C4_C4") (pintype "bidirectional+no_connect"))
    )
    (net (code "76") (name "unconnected-(J34-PadC6)") (class "Default")
      (node (ref "J34") (pin "C6") (pinfunction "C6_C6") (pintype "bidirectional+no_connect"))
    )
    (net (code "77") (name "unconnected-(J34-PadC8)") (class "Default")
      (node (ref "J34") (pin "C8") (pinfunction "C8_C8") (pintype "bidirectional+no_connect"))
    )
    (net (code "78") (name "unconnected-(J34-PadD3)") (class "Default")
      (node (ref "J34") (pin "D3") (pinfunction "D3_D3") (pintype "bidirectional+no_connect"))
    )
    (net (code "79") (name "unconnected-(J34-PadD5)") (class "Default")
      (node (ref "J34") (pin "D5") (pinfunction "D5_D5") (pintype "bidirectional+no_connect"))
    )
    (net (code "80") (name "unconnected-(J34-PadD7)") (class "Default")
      (node (ref "J34") (pin "D7") (pinfunction "D7_D7") (pintype "bidirectional"))
    )
    (net (code "81") (name "unconnected-(J34-PadE2)") (class "Default")
      (node (ref "J34") (pin "E2") (pinfunction "E2_E2") (pintype "bidirectional+no_connect"))
    )
    (net (code "82") (name "unconnected-(J34-PadE3)") (class "Default")
      (node (ref "J34") (pin "E3") (pinfunction "E3_E3") (pintype "bidirectional+no_connect"))
    )
    (net (code "83") (name "unconnected-(J34-PadE4)") (class "Default")
      (node (ref "J34") (pin "E4") (pinfunction "E4_E4") (pintype "bidirectional+no_connect"))
    )
    (net (code "84") (name "unconnected-(J34-PadE5)") (class "Default")
      (node (ref "J34") (pin "E5") (pinfunction "E5_E5") (pintype "bidirectional+no_connect"))
    )
    (net (code "85") (name "unconnected-(J34-PadE6)") (class "Default")
      (node (ref "J34") (pin "E6") (pinfunction "E6_E6") (pintype "bidirectional+no_connect"))
    )
    (net (code "86") (name "unconnected-(J34-PadE7)") (class "Default")
      (node (ref "J34") (pin "E7") (pinfunction "E7_E7") (pintype "bidirectional"))
    )
    (net (code "87") (name "unconnected-(J34-PadE8)") (class "Default")
      (node (ref "J34") (pin "E8") (pinfunction "E8_E8") (pintype "bidirectional+no_connect"))
    )
    (net (code "88") (name "unconnected-(J34-PadF2)") (class "Default")
      (node (ref "J34") (pin "F2") (pinfunction "F2_F2") (pintype "bidirectional+no_connect"))
    )
    (net (code "89") (name "unconnected-(J34-PadF4)") (class "Default")
      (node (ref "J34") (pin "F4") (pinfunction "F4_F4") (pintype "bidirectional+no_connect"))
    )
    (net (code "90") (name "unconnected-(J34-PadF6)") (class "Default")
      (node (ref "J34") (pin "F6") (pinfunction "F6_F6") (pintype "bidirectional+no_connect"))
    )
    (net (code "91") (name "unconnected-(J34-PadF8)") (class "Default")
      (node (ref "J34") (pin "F8") (pinfunction "F8_F8") (pintype "bidirectional+no_connect"))
    )
    (net (code "92") (name "unconnected-(J34-PadG3)") (class "Default")
      (node (ref "J34") (pin "G3") (pinfunction "G3_G3") (pintype "bidirectional+no_connect"))
    )
    (net (code "93") (name "unconnected-(J34-PadG5)") (class "Default")
      (node (ref "J34") (pin "G5") (pinfunction "G5_G5") (pintype "bidirectional+no_connect"))
    )
    (net (code "94") (name "unconnected-(J34-PadG7)") (class "Default")
      (node (ref "J34") (pin "G7") (pinfunction "G7_G7") (pintype "bidirectional"))
    )
    (net (code "95") (name "unconnected-(J34-PadH2)") (class "Default")
      (node (ref "J34") (pin "H2") (pinfunction "H2_H2") (pintype "bidirectional+no_connect"))
    )
    (net (code "96") (name "unconnected-(J34-PadH3)") (class "Default")
      (node (ref "J34") (pin "H3") (pinfunction "H3_H3") (pintype "bidirectional+no_connect"))
    )
    (net (code "97") (name "unconnected-(J34-PadH4)") (class "Default")
      (node (ref "J34") (pin "H4") (pinfunction "H4_H4") (pintype "bidirectional+no_connect"))
    )
    (net (code "98") (name "unconnected-(J34-PadH5)") (class "Default")
      (node (ref "J34") (pin "H5") (pinfunction "H5_H5") (pintype "bidirectional+no_connect"))
    )
    (net (code "99") (name "unconnected-(J34-PadH6)") (class "Default")
      (node (ref "J34") (pin "H6") (pinfunction "H6_H6") (pintype "bidirectional+no_connect"))
    )
    (net (code "100") (name "unconnected-(J34-PadH7)") (class "Default")
      (node (ref "J34") (pin "H7") (pinfunction "H7_H7") (pintype "bidirectional"))
    )
    (net (code "101") (name "unconnected-(J34-PadH8)") (class "Default")
      (node (ref "J34") (pin "H8") (pinfunction "H8_H8") (pintype "bidirectional+no_connect"))
    )
    (net (code "102") (name "unconnected-(J34-PadI2)") (class "Default")
      (node (ref "J34") (pin "I2") (pinfunction "I2_I2") (pintype "bidirectional+no_connect"))
    )
    (net (code "103") (name "unconnected-(J34-PadI4)") (class "Default")
      (node (ref "J34") (pin "I4") (pinfunction "I4_I4") (pintype "bidirectional+no_connect"))
    )
    (net (code "104") (name "unconnected-(J34-PadI6)") (class "Default")
      (node (ref "J34") (pin "I6") (pinfunction "I6_I6") (pintype "bidirectional+no_connect"))
    )
    (net (code "105") (name "unconnected-(J34-PadI8)") (class "Default")
      (node (ref "J34") (pin "I8") (pinfunction "I8_I8") (pintype "bidirectional+no_connect"))
    )
    (net (code "106") (name "unconnected-(J34-PadJ3)") (class "Default")
      (node (ref "J34") (pin "J3") (pinfunction "J3_J3") (pintype "bidirectional+no_connect"))
    )
    (net (code "107") (name "unconnected-(J34-PadJ5)") (class "Default")
      (node (ref "J34") (pin "J5") (pinfunction "J5_J5") (pintype "bidirectional+no_connect"))
    )
    (net (code "108") (name "unconnected-(J34-PadJ7)") (class "Default")
      (node (ref "J34") (pin "J7") (pinfunction "J7_J7") (pintype "bidirectional"))
    )
    (net (code "109") (name "unconnected-(J34-PadK2)") (class "Default")
      (node (ref "J34") (pin "K2") (pinfunction "K2_K2") (pintype "bidirectional+no_connect"))
    )
    (net (code "110") (name "unconnected-(J34-PadK3)") (class "Default")
      (node (ref "J34") (pin "K3") (pinfunction "K3_K3") (pintype "bidirectional+no_connect"))
    )
    (net (code "111") (name "unconnected-(J34-PadK4)") (class "Default")
      (node (ref "J34") (pin "K4") (pinfunction "K4_K4") (pintype "bidirectional+no_connect"))
    )
    (net (code "112") (name "unconnected-(J34-PadK5)") (class "Default")
      (node (ref "J34") (pin "K5") (pinfunction "K5_K5") (pintype "bidirectional+no_connect"))
    )
    (net (code "113") (name "unconnected-(J34-PadK6)") (class "Default")
      (node (ref "J34") (pin "K6") (pinfunction "K6_K6") (pintype "bidirectional+no_connect"))
    )
    (net (code "114") (name "unconnected-(J34-PadK7)") (class "Default")
      (node (ref "J34") (pin "K7") (pinfunction "K7_K7") (pintype "bidirectional"))
    )
    (net (code "115") (name "unconnected-(J34-PadK8)") (class "Default")
      (node (ref "J34") (pin "K8") (pinfunction "K8_K8") (pintype "bidirectional+no_connect"))
    )
    (net (code "116") (name "unconnected-(J34-PadL2)") (class "Default")
      (node (ref "J34") (pin "L2") (pinfunction "L2_L2") (pintype "bidirectional+no_connect"))
    )
    (net (code "117") (name "unconnected-(J34-PadL4)") (class "Default")
      (node (ref "J34") (pin "L4") (pinfunction "L4_L4") (pintype "bidirectional+no_connect"))
    )
    (net (code "118") (name "unconnected-(J34-PadL6)") (class "Default")
      (node (ref "J34") (pin "L6") (pinfunction "L6_L6") (pintype "bidirectional+no_connect"))
    )
    (net (code "119") (name "unconnected-(J34-PadL8)") (class "Default")
      (node (ref "J34") (pin "L8") (pinfunction "L8_L8") (pintype "bidirectional+no_connect"))
    )
  )
)
